# Motee.net
KiCad netlist of a schematic drawn in EAGLE
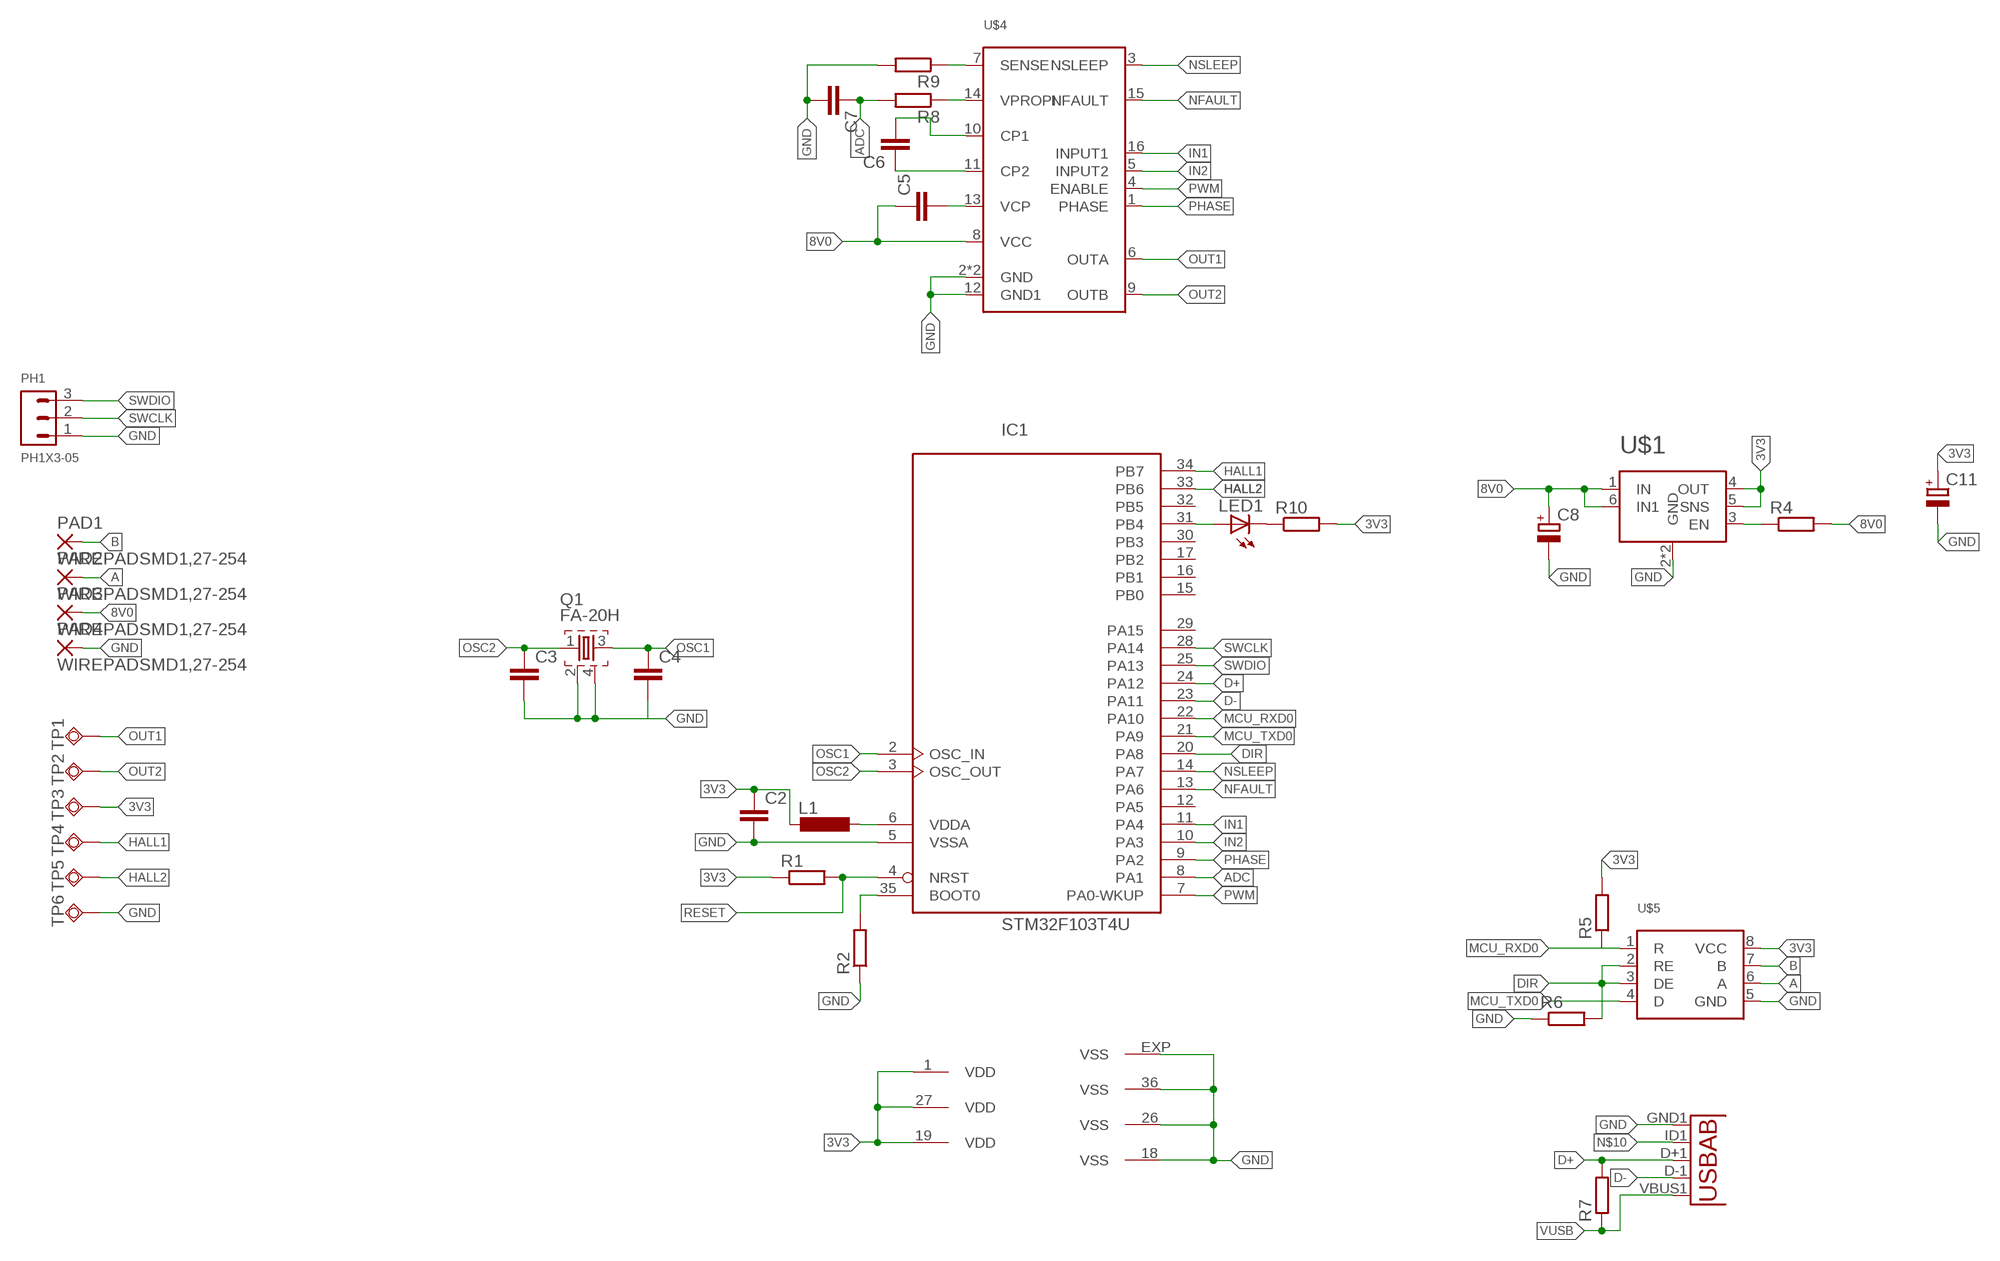
[diagram p0: schematic, sheet 1]

(export (version "E")
  (design (tool "Eeschema 10.0.6"))
  (components
    (comp (ref "C2")
      (value "C-EUC0402K")
      (footprint "eagle-import:C0402K")
      (libsource (lib "eagle-import") (part "C-EUC0402K"))
    )
    (comp (ref "C3")
      (value "C-EUC0402K")
      (footprint "eagle-import:C0402K")
      (libsource (lib "eagle-import") (part "C-EUC0402K"))
    )
    (comp (ref "C4")
      (value "C-EUC0402K")
      (footprint "eagle-import:C0402K")
      (libsource (lib "eagle-import") (part "C-EUC0402K"))
    )
    (comp (ref "C5")
      (value "C-EUC0402K")
      (footprint "eagle-import:C0402K")
      (libsource (lib "eagle-import") (part "C-EUC0402K"))
    )
    (comp (ref "C6")
      (value "C-EUC0402K")
      (footprint "eagle-import:C0402K")
      (libsource (lib "eagle-import") (part "C-EUC0402K"))
    )
    (comp (ref "C7")
      (value "C-EUC0402K")
      (footprint "eagle-import:C0402K")
      (libsource (lib "eagle-import") (part "C-EUC0402K"))
    )
    (comp (ref "C8")
      (value "CPOL-EUB/3528-21R")
      (footprint "eagle-import:B_3528-21R")
      (libsource (lib "eagle-import") (part "CPOL-EUB/3528-21R"))
    )
    (comp (ref "C11")
      (value "CPOL-EUB/3528-21R")
      (footprint "eagle-import:B_3528-21R")
      (libsource (lib "eagle-import") (part "CPOL-EUB/3528-21R"))
    )
    (comp (ref "IC1")
      (value "STM32F103T4U")
      (footprint "eagle-import:VFQFPN36")
      (libsource (lib "eagle-import") (part "STM32F103TU4"))
    )
    (comp (ref "L1")
      (value "L-EUL2012C")
      (footprint "eagle-import:L2012C")
      (libsource (lib "eagle-import") (part "L-EUL2012C"))
    )
    (comp (ref "LED1")
      (value "LEDCHIP-LED0603")
      (footprint "eagle-import:CHIP-LED0603")
      (libsource (lib "eagle-import") (part "LEDCHIP-LED0603"))
    )
    (comp (ref "PAD1")
      (value "WIREPADSMD1,27-254")
      (footprint "eagle-import:SMD1,27-2,54")
      (libsource (lib "eagle-import") (part "WIREPADSMD1,27-254"))
    )
    (comp (ref "PAD2")
      (value "WIREPADSMD1,27-254")
      (footprint "eagle-import:SMD1,27-2,54")
      (libsource (lib "eagle-import") (part "WIREPADSMD1,27-254"))
    )
    (comp (ref "PAD3")
      (value "WIREPADSMD1,27-254")
      (footprint "eagle-import:SMD1,27-2,54")
      (libsource (lib "eagle-import") (part "WIREPADSMD1,27-254"))
    )
    (comp (ref "PAD4")
      (value "WIREPADSMD1,27-254")
      (footprint "eagle-import:SMD1,27-2,54")
      (libsource (lib "eagle-import") (part "WIREPADSMD1,27-254"))
    )
    (comp (ref "PH1")
      (value "PH1X3-05")
      (footprint "eagle-import:PH005-1-3")
      (libsource (lib "eagle-import") (part "PH1X3-05"))
    )
    (comp (ref "Q1")
      (value "FA-20H")
      (footprint "eagle-import:FA-20H")
      (libsource (lib "eagle-import") (part "FA-20H"))
    )
    (comp (ref "R1")
      (value "R-EU_R0402")
      (footprint "eagle-import:R0402")
      (libsource (lib "eagle-import") (part "R-EU_R0402"))
    )
    (comp (ref "R2")
      (value "R-EU_R0402")
      (footprint "eagle-import:R0402")
      (libsource (lib "eagle-import") (part "R-EU_R0402"))
    )
    (comp (ref "R4")
      (value "R-EU_R0402")
      (footprint "eagle-import:R0402")
      (libsource (lib "eagle-import") (part "R-EU_R0402"))
    )
    (comp (ref "R5")
      (value "R-EU_R0402")
      (footprint "eagle-import:R0402")
      (libsource (lib "eagle-import") (part "R-EU_R0402"))
    )
    (comp (ref "R6")
      (value "R-EU_R0402")
      (footprint "eagle-import:R0402")
      (libsource (lib "eagle-import") (part "R-EU_R0402"))
    )
    (comp (ref "R7")
      (value "R-EU_R0402")
      (footprint "eagle-import:R0402")
      (libsource (lib "eagle-import") (part "R-EU_R0402"))
    )
    (comp (ref "R8")
      (value "R-EU_R0402")
      (footprint "eagle-import:R0402")
      (libsource (lib "eagle-import") (part "R-EU_R0402"))
    )
    (comp (ref "R9")
      (value "R-EU_R0402")
      (footprint "eagle-import:R0402")
      (libsource (lib "eagle-import") (part "R-EU_R0402"))
    )
    (comp (ref "R10")
      (value "R-EU_R0402")
      (footprint "eagle-import:R0402")
      (libsource (lib "eagle-import") (part "R-EU_R0402"))
    )
    (comp (ref "TP1")
      (value "TPSQTP20SQ")
      (footprint "eagle-import:TP20SQ")
      (libsource (lib "eagle-import") (part "TPSQTP20SQ"))
    )
    (comp (ref "TP2")
      (value "TPSQTP20SQ")
      (footprint "eagle-import:TP20SQ")
      (libsource (lib "eagle-import") (part "TPSQTP20SQ"))
    )
    (comp (ref "TP3")
      (value "TPSQTP20SQ")
      (footprint "eagle-import:TP20SQ")
      (libsource (lib "eagle-import") (part "TPSQTP20SQ"))
    )
    (comp (ref "TP4")
      (value "TPSQTP20SQ")
      (footprint "eagle-import:TP20SQ")
      (libsource (lib "eagle-import") (part "TPSQTP20SQ"))
    )
    (comp (ref "TP5")
      (value "TPSQTP20SQ")
      (footprint "eagle-import:TP20SQ")
      (libsource (lib "eagle-import") (part "TPSQTP20SQ"))
    )
    (comp (ref "TP6")
      (value "TPSQTP20SQ")
      (footprint "eagle-import:TP20SQ")
      (libsource (lib "eagle-import") (part "TPSQTP20SQ"))
    )
    (comp (ref "U$1")
      (value "LP38693")
      (footprint "eagle-import:LP38693")
      (libsource (lib "eagle-import") (part "LP38693"))
    )
    (comp (ref "U$4")
      (value "DRV8801")
      (footprint "eagle-import:WQFN-16")
      (libsource (lib "eagle-import") (part "DRV8801"))
    )
    (comp (ref "U$5")
      (value "MAX22501EATA")
      (footprint "eagle-import:TDFN-8")
      (libsource (lib "eagle-import") (part "MAX22501EATA"))
    )
    (comp (ref "U1")
      (value "USB\"\"")
      (footprint "eagle-import:USB-MICRO-SMD")
      (libsource (lib "eagle-import") (part "USB{dblquote}{dblquote}"))
    )
  )
  (nets
    (net (code "1") (name "3V3") (class "Default")
      (node (ref "C11") (pin "+") (pinfunction "+_+") (pintype "passive"))
      (node (ref "C2") (pin "1") (pinfunction "1_1") (pintype "passive"))
      (node (ref "IC1") (pin "1") (pinfunction "VDD_1") (pintype "power_in"))
      (node (ref "IC1") (pin "19") (pinfunction "VDD_19") (pintype "power_in"))
      (node (ref "IC1") (pin "27") (pinfunction "VDD_27") (pintype "power_in"))
      (node (ref "L1") (pin "2") (pinfunction "2_2") (pintype "passive"))
      (node (ref "R1") (pin "1") (pinfunction "1_1") (pintype "passive"))
      (node (ref "R10") (pin "2") (pinfunction "2_2") (pintype "passive"))
      (node (ref "R5") (pin "2") (pinfunction "2_2") (pintype "passive"))
      (node (ref "TP3") (pin "TP") (pinfunction "TP_TP") (pintype "input"))
      (node (ref "U$1") (pin "4") (pinfunction "OUT_4") (pintype "bidirectional"))
      (node (ref "U$1") (pin "5") (pinfunction "SNS_5") (pintype "bidirectional"))
      (node (ref "U$5") (pin "8") (pinfunction "VCC_8") (pintype "bidirectional"))
    )
    (net (code "2") (name "8V0") (class "Default")
      (node (ref "C5") (pin "1") (pinfunction "1_1") (pintype "passive"))
      (node (ref "C8") (pin "+") (pinfunction "+_+") (pintype "passive"))
      (node (ref "PAD3") (pin "1") (pinfunction "P_1") (pintype "passive"))
      (node (ref "R4") (pin "2") (pinfunction "2_2") (pintype "passive"))
      (node (ref "U$1") (pin "1") (pinfunction "IN_1") (pintype "bidirectional"))
      (node (ref "U$1") (pin "6") (pinfunction "IN1_6") (pintype "bidirectional"))
      (node (ref "U$4") (pin "8") (pinfunction "VCC_8") (pintype "bidirectional"))
    )
    (net (code "3") (name "A") (class "Default")
      (node (ref "PAD2") (pin "1") (pinfunction "P_1") (pintype "passive"))
      (node (ref "U$5") (pin "6") (pinfunction "A_6") (pintype "bidirectional"))
    )
    (net (code "4") (name "ADC") (class "Default")
      (node (ref "C7") (pin "1") (pinfunction "1_1") (pintype "passive"))
      (node (ref "IC1") (pin "8") (pinfunction "PA1_8") (pintype "bidirectional"))
      (node (ref "R8") (pin "2") (pinfunction "2_2") (pintype "passive"))
    )
    (net (code "5") (name "B") (class "Default")
      (node (ref "PAD1") (pin "1") (pinfunction "P_1") (pintype "passive"))
      (node (ref "U$5") (pin "7") (pinfunction "B_7") (pintype "bidirectional"))
    )
    (net (code "6") (name "D+") (class "Default")
      (node (ref "IC1") (pin "24") (pinfunction "PA12_24") (pintype "bidirectional"))
      (node (ref "R7") (pin "2") (pinfunction "2_2") (pintype "passive"))
      (node (ref "U1") (pin "D+1") (pinfunction "D+_D+1") (pintype "bidirectional"))
    )
    (net (code "7") (name "D-") (class "Default")
      (node (ref "IC1") (pin "23") (pinfunction "PA11_23") (pintype "bidirectional"))
      (node (ref "U1") (pin "D-1") (pinfunction "D-_D-1") (pintype "bidirectional"))
    )
    (net (code "8") (name "DIR") (class "Default")
      (node (ref "IC1") (pin "20") (pinfunction "PA8_20") (pintype "bidirectional"))
      (node (ref "R6") (pin "2") (pinfunction "2_2") (pintype "passive"))
      (node (ref "U$5") (pin "2") (pinfunction "RE_2") (pintype "bidirectional"))
      (node (ref "U$5") (pin "3") (pinfunction "DE_3") (pintype "bidirectional"))
    )
    (net (code "9") (name "GND") (class "Default")
      (node (ref "C11") (pin "-") (pinfunction "-_-") (pintype "passive"))
      (node (ref "C2") (pin "2") (pinfunction "2_2") (pintype "passive"))
      (node (ref "C3") (pin "2") (pinfunction "2_2") (pintype "passive"))
      (node (ref "C4") (pin "2") (pinfunction "2_2") (pintype "passive"))
      (node (ref "C7") (pin "2") (pinfunction "2_2") (pintype "passive"))
      (node (ref "C8") (pin "-") (pinfunction "-_-") (pintype "passive"))
      (node (ref "IC1") (pin "18") (pinfunction "VSS_18") (pintype "power_in"))
      (node (ref "IC1") (pin "26") (pinfunction "VSS_26") (pintype "power_in"))
      (node (ref "IC1") (pin "36") (pinfunction "VSS_36") (pintype "power_in"))
      (node (ref "IC1") (pin "5") (pinfunction "VSSA_5") (pintype "power_in"))
      (node (ref "IC1") (pin "EXP") (pinfunction "VSS_EXP") (pintype "power_in"))
      (node (ref "PAD4") (pin "1") (pinfunction "P_1") (pintype "passive"))
      (node (ref "PH1") (pin "1") (pinfunction "1_1") (pintype "bidirectional"))
      (node (ref "Q1") (pin "2") (pinfunction "2_2") (pintype "passive"))
      (node (ref "Q1") (pin "4") (pinfunction "4_4") (pintype "passive"))
      (node (ref "R2") (pin "1") (pinfunction "1_1") (pintype "passive"))
      (node (ref "R6") (pin "1") (pinfunction "1_1") (pintype "passive"))
      (node (ref "R9") (pin "2") (pinfunction "2_2") (pintype "passive"))
      (node (ref "TP6") (pin "TP") (pinfunction "TP_TP") (pintype "input"))
      (node (ref "U$1") (pin "2") (pinfunction "GND_2") (pintype "bidirectional"))
      (node (ref "U$1") (pin "7") (pinfunction "GND_7") (pintype "bidirectional"))
      (node (ref "U$4") (pin "12") (pinfunction "GND1_12") (pintype "bidirectional"))
      (node (ref "U$4") (pin "17") (pinfunction "GND_17") (pintype "bidirectional"))
      (node (ref "U$4") (pin "2") (pinfunction "GND_2") (pintype "bidirectional"))
      (node (ref "U$5") (pin "5") (pinfunction "GND_5") (pintype "bidirectional"))
      (node (ref "U1") (pin "GND1") (pinfunction "GND_GND1") (pintype "bidirectional"))
    )
    (net (code "10") (name "HALL1") (class "Default")
      (node (ref "IC1") (pin "34") (pinfunction "PB7_34") (pintype "bidirectional"))
      (node (ref "TP4") (pin "TP") (pinfunction "TP_TP") (pintype "input"))
    )
    (net (code "11") (name "HALL2") (class "Default")
      (node (ref "IC1") (pin "33") (pinfunction "PB6_33") (pintype "bidirectional"))
      (node (ref "TP5") (pin "TP") (pinfunction "TP_TP") (pintype "input"))
    )
    (net (code "12") (name "IN1") (class "Default")
      (node (ref "IC1") (pin "11") (pinfunction "PA4_11") (pintype "bidirectional"))
      (node (ref "U$4") (pin "16") (pinfunction "INPUT1_16") (pintype "bidirectional"))
    )
    (net (code "13") (name "IN2") (class "Default")
      (node (ref "IC1") (pin "10") (pinfunction "PA3_10") (pintype "bidirectional"))
      (node (ref "U$4") (pin "5") (pinfunction "INPUT2_5") (pintype "bidirectional"))
    )
    (net (code "14") (name "MCU_RXD0") (class "Default")
      (node (ref "IC1") (pin "22") (pinfunction "PA10_22") (pintype "bidirectional"))
      (node (ref "R5") (pin "1") (pinfunction "1_1") (pintype "passive"))
      (node (ref "U$5") (pin "1") (pinfunction "R_1") (pintype "bidirectional"))
    )
    (net (code "15") (name "MCU_TXD0") (class "Default")
      (node (ref "IC1") (pin "21") (pinfunction "PA9_21") (pintype "bidirectional"))
      (node (ref "U$5") (pin "4") (pinfunction "D_4") (pintype "bidirectional"))
    )
    (net (code "16") (name "N$10") (class "Default")
      (node (ref "U1") (pin "ID1") (pinfunction "USBID_ID1") (pintype "bidirectional"))
    )
    (net (code "17") (name "NFAULT") (class "Default")
      (node (ref "IC1") (pin "13") (pinfunction "PA6_13") (pintype "bidirectional"))
      (node (ref "U$4") (pin "15") (pinfunction "NFAULT_15") (pintype "bidirectional"))
    )
    (net (code "18") (name "NSLEEP") (class "Default")
      (node (ref "IC1") (pin "14") (pinfunction "PA7_14") (pintype "bidirectional"))
      (node (ref "U$4") (pin "3") (pinfunction "NSLEEP_3") (pintype "bidirectional"))
    )
    (net (code "19") (name "Net-(IC1A-BOOT0)") (class "Default")
      (node (ref "IC1") (pin "35") (pinfunction "BOOT0_35") (pintype "input"))
      (node (ref "R2") (pin "2") (pinfunction "2_2") (pintype "passive"))
    )
    (net (code "20") (name "Net-(IC1A-PB4)") (class "Default")
      (node (ref "IC1") (pin "31") (pinfunction "PB4_31") (pintype "bidirectional"))
      (node (ref "LED1") (pin "A") (pinfunction "A_A") (pintype "passive"))
    )
    (net (code "21") (name "Net-(IC1A-VDDA)") (class "Default")
      (node (ref "IC1") (pin "6") (pinfunction "VDDA_6") (pintype "power_in"))
      (node (ref "L1") (pin "1") (pinfunction "1_1") (pintype "passive"))
    )
    (net (code "22") (name "Net-(LED1-PadC)") (class "Default")
      (node (ref "LED1") (pin "C") (pinfunction "C_C") (pintype "passive"))
      (node (ref "R10") (pin "1") (pinfunction "1_1") (pintype "passive"))
    )
    (net (code "23") (name "Net-(U$1-EN)") (class "Default")
      (node (ref "R4") (pin "1") (pinfunction "1_1") (pintype "passive"))
      (node (ref "U$1") (pin "3") (pinfunction "EN_3") (pintype "bidirectional"))
    )
    (net (code "24") (name "Net-(U$4-CP1)") (class "Default")
      (node (ref "C6") (pin "2") (pinfunction "2_2") (pintype "passive"))
      (node (ref "U$4") (pin "10") (pinfunction "CP1_10") (pintype "bidirectional"))
    )
    (net (code "25") (name "Net-(U$4-CP2)") (class "Default")
      (node (ref "C6") (pin "1") (pinfunction "1_1") (pintype "passive"))
      (node (ref "U$4") (pin "11") (pinfunction "CP2_11") (pintype "bidirectional"))
    )
    (net (code "26") (name "Net-(U$4-SENSE)") (class "Default")
      (node (ref "R9") (pin "1") (pinfunction "1_1") (pintype "passive"))
      (node (ref "U$4") (pin "7") (pinfunction "SENSE_7") (pintype "bidirectional"))
    )
    (net (code "27") (name "Net-(U$4-VCP)") (class "Default")
      (node (ref "C5") (pin "2") (pinfunction "2_2") (pintype "passive"))
      (node (ref "U$4") (pin "13") (pinfunction "VCP_13") (pintype "bidirectional"))
    )
    (net (code "28") (name "Net-(U$4-VPROPI)") (class "Default")
      (node (ref "R8") (pin "1") (pinfunction "1_1") (pintype "passive"))
      (node (ref "U$4") (pin "14") (pinfunction "VPROPI_14") (pintype "bidirectional"))
    )
    (net (code "29") (name "OSC1") (class "Default")
      (node (ref "C4") (pin "1") (pinfunction "1_1") (pintype "passive"))
      (node (ref "IC1") (pin "2") (pinfunction "OSC_IN_2") (pintype "bidirectional"))
      (node (ref "Q1") (pin "3") (pinfunction "3_3") (pintype "passive"))
    )
    (net (code "30") (name "OSC2") (class "Default")
      (node (ref "C3") (pin "1") (pinfunction "1_1") (pintype "passive"))
      (node (ref "IC1") (pin "3") (pinfunction "OSC_OUT_3") (pintype "bidirectional"))
      (node (ref "Q1") (pin "1") (pinfunction "1_1") (pintype "passive"))
    )
    (net (code "31") (name "OUT1") (class "Default")
      (node (ref "TP1") (pin "TP") (pinfunction "TP_TP") (pintype "input"))
      (node (ref "U$4") (pin "6") (pinfunction "OUTA_6") (pintype "bidirectional"))
    )
    (net (code "32") (name "OUT2") (class "Default")
      (node (ref "TP2") (pin "TP") (pinfunction "TP_TP") (pintype "input"))
      (node (ref "U$4") (pin "9") (pinfunction "OUTB_9") (pintype "bidirectional"))
    )
    (net (code "33") (name "PHASE") (class "Default")
      (node (ref "IC1") (pin "9") (pinfunction "PA2_9") (pintype "bidirectional"))
      (node (ref "U$4") (pin "1") (pinfunction "PHASE_1") (pintype "bidirectional"))
    )
    (net (code "34") (name "PWM") (class "Default")
      (node (ref "IC1") (pin "7") (pinfunction "PA0-WKUP_7") (pintype "bidirectional"))
      (node (ref "U$4") (pin "4") (pinfunction "ENABLE_4") (pintype "bidirectional"))
    )
    (net (code "35") (name "RESET") (class "Default")
      (node (ref "IC1") (pin "4") (pinfunction "NRST_4") (pintype "bidirectional"))
      (node (ref "R1") (pin "2") (pinfunction "2_2") (pintype "passive"))
    )
    (net (code "36") (name "SWCLK") (class "Default")
      (node (ref "IC1") (pin "28") (pinfunction "PA14_28") (pintype "bidirectional"))
      (node (ref "PH1") (pin "2") (pinfunction "2_2") (pintype "bidirectional"))
    )
    (net (code "37") (name "SWDIO") (class "Default")
      (node (ref "IC1") (pin "25") (pinfunction "PA13_25") (pintype "bidirectional"))
      (node (ref "PH1") (pin "3") (pinfunction "3_3") (pintype "bidirectional"))
    )
    (net (code "38") (name "VUSB") (class "Default")
      (node (ref "R7") (pin "1") (pinfunction "1_1") (pintype "passive"))
      (node (ref "U1") (pin "VBUS1") (pinfunction "VBUS_VBUS1") (pintype "bidirectional"))
    )
    (net (code "39") (name "unconnected-(IC1A-PA5-Pad12)") (class "Default")
      (node (ref "IC1") (pin "12") (pinfunction "PA5_12") (pintype "bidirectional"))
    )
    (net (code "40") (name "unconnected-(IC1A-PA15-Pad29)") (class "Default")
      (node (ref "IC1") (pin "29") (pinfunction "PA15_29") (pintype "bidirectional"))
    )
    (net (code "41") (name "unconnected-(IC1A-PB0-Pad15)") (class "Default")
      (node (ref "IC1") (pin "15") (pinfunction "PB0_15") (pintype "bidirectional"))
    )
    (net (code "42") (name "unconnected-(IC1A-PB1-Pad16)") (class "Default")
      (node (ref "IC1") (pin "16") (pinfunction "PB1_16") (pintype "bidirectional"))
    )
    (net (code "43") (name "unconnected-(IC1A-PB2-Pad17)") (class "Default")
      (node (ref "IC1") (pin "17") (pinfunction "PB2_17") (pintype "bidirectional"))
    )
    (net (code "44") (name "unconnected-(IC1A-PB3-Pad30)") (class "Default")
      (node (ref "IC1") (pin "30") (pinfunction "PB3_30") (pintype "bidirectional"))
    )
    (net (code "45") (name "unconnected-(IC1A-PB5-Pad32)") (class "Default")
      (node (ref "IC1") (pin "32") (pinfunction "PB5_32") (pintype "bidirectional"))
    )
  )
)
